# ITU_Rocket_Main_Board.net
KiCad netlist of a schematic drawn in Altium Designer
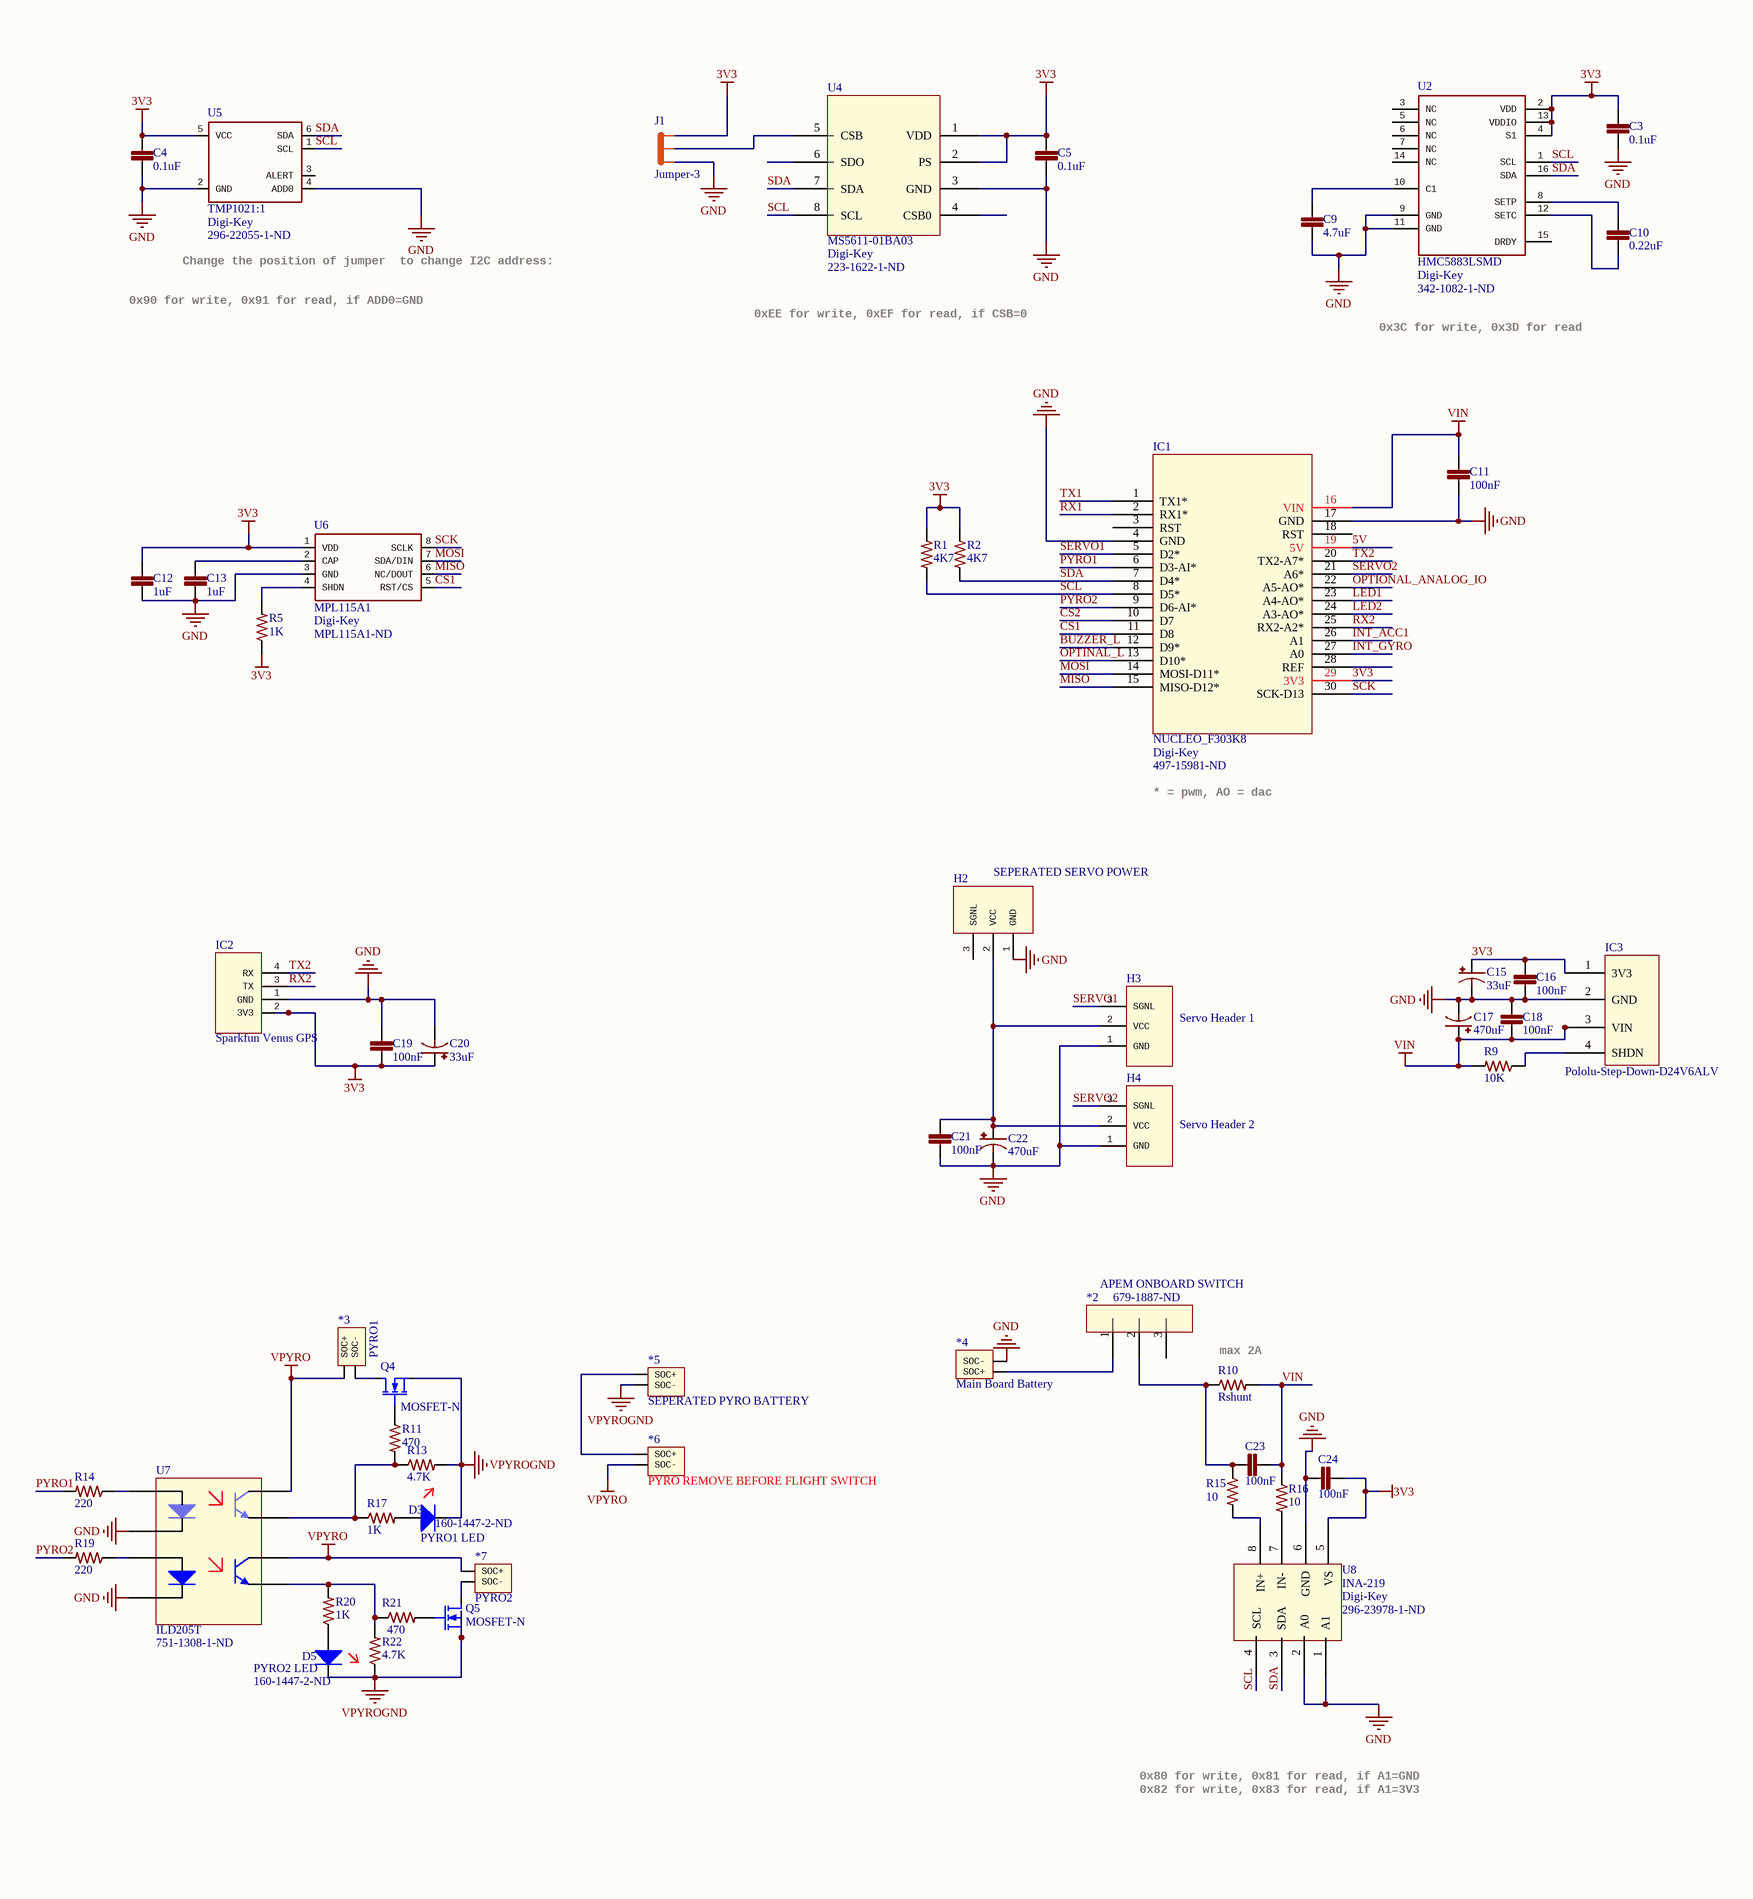
[diagram p0: ITU_Rocket_Main_Board.SchDoc, left]
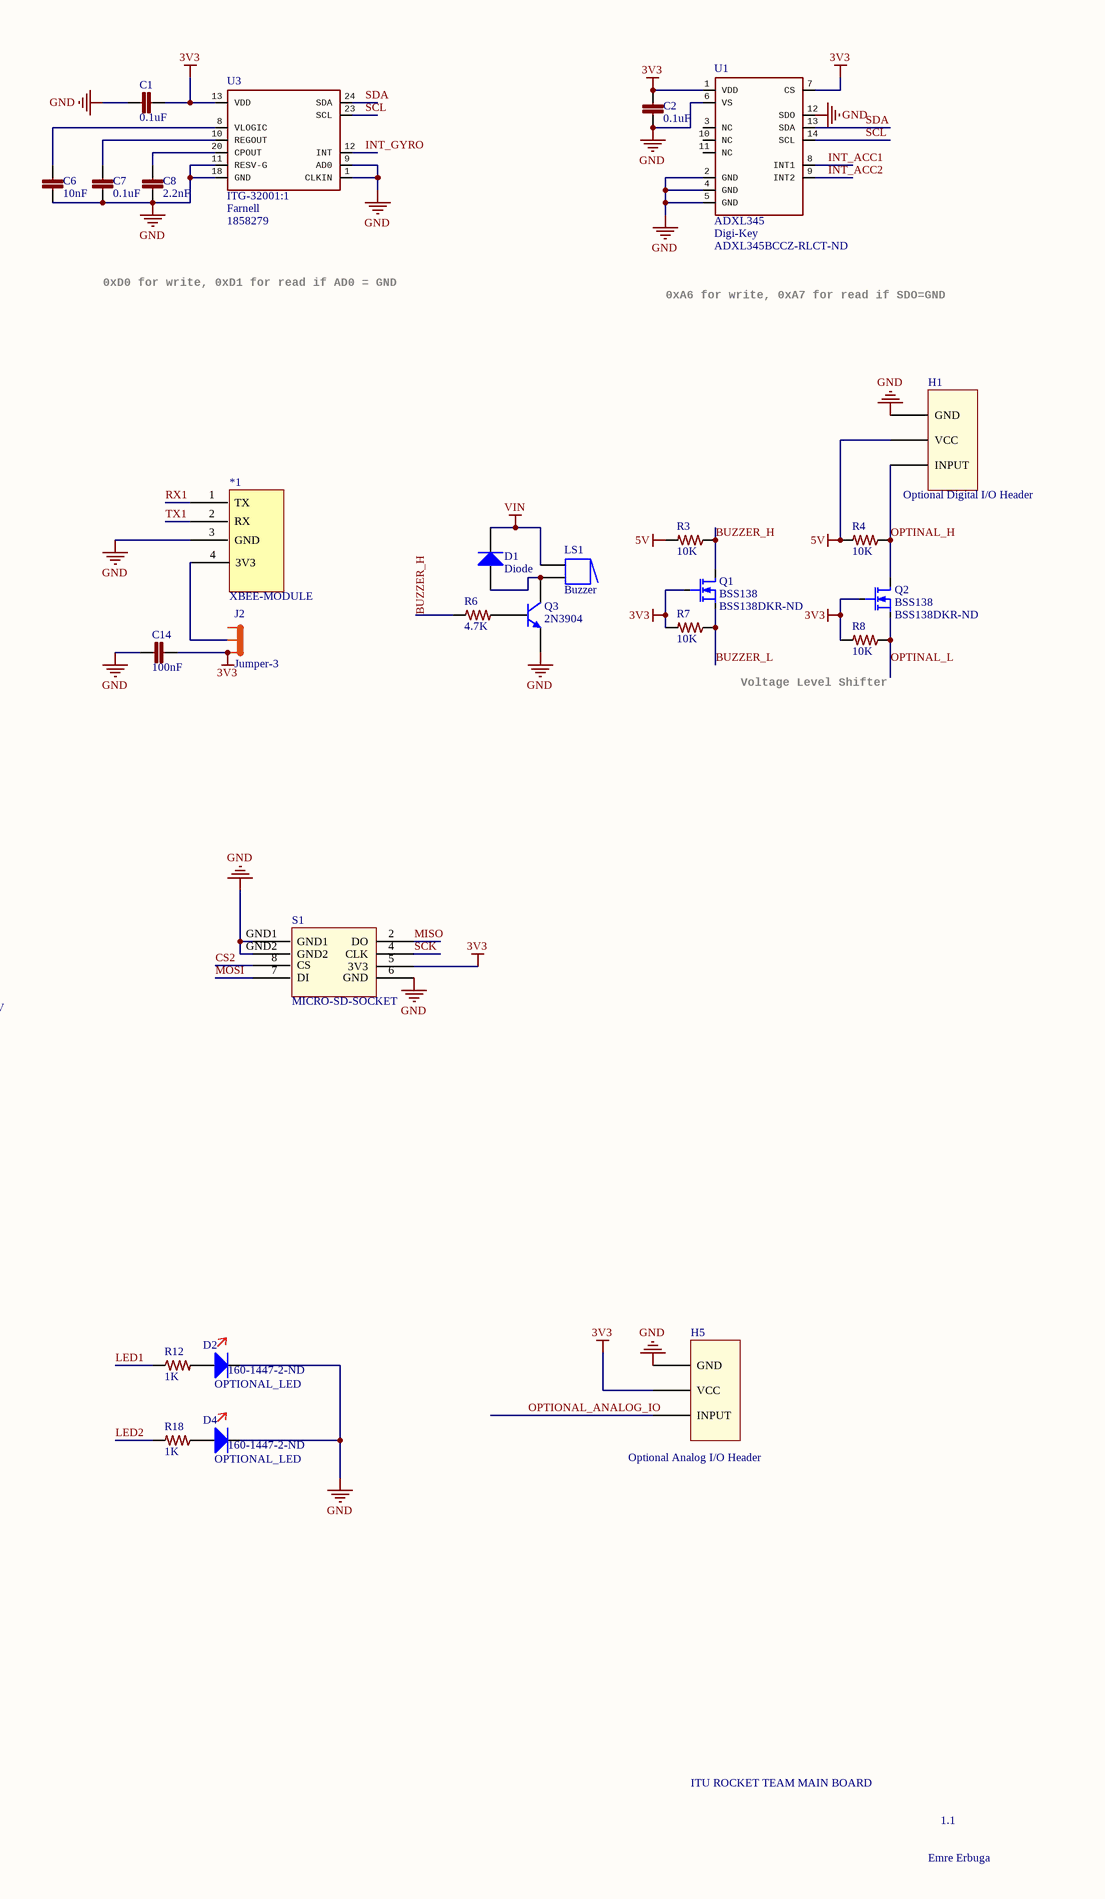
[diagram p1: ITU_Rocket_Main_Board.SchDoc, right]

(export (version "E")
  (design (tool "Eeschema 10.0.6"))
  (components
    (comp (ref "*1")
      (value "XBEE-MODULE")
      (footprint "XBEE-MODULE")
      (libsource (lib "ITU_Rocket_Main_Board") (part "XBEE-MODULE"))
    )
    (comp (ref "*2")
      (value "APEM ONBOARD SWITCH")
      (footprint "Switch_5.08")
      (description "SWITCH SLIDE SPDT 4A 125V")
      (fields
        (field (name "MANUFACTURER") "Apem Inc.")
        (field (name "MANUFACTURER PART NUMBER") "25136NAH")
        (field (name "SUPPLIER PART NUMBER 1") "679-1887-ND")
      )
      (libsource (lib "ITU_Rocket_Main_Board") (part "25136NAH"))
    )
    (comp (ref "*3")
      (value "PYRO1")
      (footprint "POWER_SOCKET")
      (libsource (lib "ITU_Rocket_Main_Board") (part "Power-Terminal"))
    )
    (comp (ref "*4")
      (value "Main Board Battery")
      (footprint "POWER_SOCKET")
      (libsource (lib "") (part "Power-Terminal_2"))
    )
    (comp (ref "*5")
      (value "SEPERATED PYRO BATTERY")
      (footprint "POWER_SOCKET")
      (libsource (lib "") (part "Power-Terminal_1"))
    )
    (comp (ref "*6")
      (value "PYRO REMOVE BEFORE FLIGHT SWITCH")
      (footprint "POWER_SOCKET")
      (libsource (lib "") (part "Power-Terminal_1"))
    )
    (comp (ref "*7")
      (value "PYRO2")
      (footprint "POWER_SOCKET")
      (libsource (lib "") (part "Power-Terminal_1"))
    )
    (comp (ref "C1")
      (value "0.1uF")
      (footprint "0603-CAP")
      (fields
        (field (name "MANUFACTURER") "Fairchild Semiconductor")
        (field (name "MANUFACTURER PART NUMBER") "BSS138")
      )
      (libsource (lib "") (part "CAP0603-CAP_1"))
    )
    (comp (ref "C2")
      (value "0.1uF")
      (footprint "0603-CAP")
      (fields
        (field (name "MANUFACTURER") "Fairchild Semiconductor")
        (field (name "MANUFACTURER PART NUMBER") "BSS138")
      )
      (libsource (lib "ITU_Rocket_Main_Board") (part "CAP0603-CAP"))
    )
    (comp (ref "C3")
      (value "0.1uF")
      (footprint "0603-CAP")
      (fields
        (field (name "MANUFACTURER") "Fairchild Semiconductor")
        (field (name "MANUFACTURER PART NUMBER") "BSS138")
      )
      (libsource (lib "ITU_Rocket_Main_Board") (part "CAP0603-CAP"))
    )
    (comp (ref "C4")
      (value "0.1uF")
      (footprint "0603-CAP")
      (fields
        (field (name "MANUFACTURER") "Fairchild Semiconductor")
        (field (name "MANUFACTURER PART NUMBER") "BSS138")
      )
      (libsource (lib "ITU_Rocket_Main_Board") (part "CAP0603-CAP"))
    )
    (comp (ref "C5")
      (value "0.1uF")
      (footprint "0603-CAP")
      (fields
        (field (name "MANUFACTURER") "Fairchild Semiconductor")
        (field (name "MANUFACTURER PART NUMBER") "BSS138")
      )
      (libsource (lib "ITU_Rocket_Main_Board") (part "CAP0603-CAP"))
    )
    (comp (ref "C6")
      (value "10nF")
      (footprint "0603-CAP")
      (fields
        (field (name "MANUFACTURER") "Fairchild Semiconductor")
        (field (name "MANUFACTURER PART NUMBER") "BSS138")
      )
      (libsource (lib "ITU_Rocket_Main_Board") (part "CAP0603-CAP"))
    )
    (comp (ref "C7")
      (value "0.1uF")
      (footprint "0603-CAP")
      (fields
        (field (name "MANUFACTURER") "Fairchild Semiconductor")
        (field (name "MANUFACTURER PART NUMBER") "BSS138")
      )
      (libsource (lib "ITU_Rocket_Main_Board") (part "CAP0603-CAP"))
    )
    (comp (ref "C8")
      (value "2.2nF")
      (footprint "0603-CAP")
      (fields
        (field (name "MANUFACTURER") "Fairchild Semiconductor")
        (field (name "MANUFACTURER PART NUMBER") "BSS138")
      )
      (libsource (lib "ITU_Rocket_Main_Board") (part "CAP0603-CAP"))
    )
    (comp (ref "C9")
      (value "4.7uF")
      (footprint "CAP0805-NP")
      (fields
        (field (name "MANUFACTURER") "Fairchild Semiconductor")
        (field (name "MANUFACTURER PART NUMBER") "BSS138")
      )
      (libsource (lib "ITU_Rocket_Main_Board") (part "CAP0603-CAP"))
    )
    (comp (ref "C10")
      (value "0.22uF")
      (footprint "0603-CAP")
      (fields
        (field (name "MANUFACTURER") "Fairchild Semiconductor")
        (field (name "MANUFACTURER PART NUMBER") "BSS138")
      )
      (libsource (lib "ITU_Rocket_Main_Board") (part "CAP0603-CAP"))
    )
    (comp (ref "C11")
      (value "100nF")
      (footprint "0603-CAP")
      (fields
        (field (name "MANUFACTURER") "Fairchild Semiconductor")
        (field (name "MANUFACTURER PART NUMBER") "BSS138")
      )
      (libsource (lib "ITU_Rocket_Main_Board") (part "CAP0603-CAP"))
    )
    (comp (ref "C12")
      (value "1uF")
      (footprint "0603-CAP")
      (fields
        (field (name "MANUFACTURER") "Fairchild Semiconductor")
        (field (name "MANUFACTURER PART NUMBER") "BSS138")
      )
      (libsource (lib "ITU_Rocket_Main_Board") (part "CAP0603-CAP"))
    )
    (comp (ref "C13")
      (value "1uF")
      (footprint "0603-CAP")
      (fields
        (field (name "MANUFACTURER") "Fairchild Semiconductor")
        (field (name "MANUFACTURER PART NUMBER") "BSS138")
      )
      (libsource (lib "ITU_Rocket_Main_Board") (part "CAP0603-CAP"))
    )
    (comp (ref "C14")
      (value "100nF")
      (footprint "0603-CAP")
      (fields
        (field (name "MANUFACTURER") "Fairchild Semiconductor")
        (field (name "MANUFACTURER PART NUMBER") "BSS138")
      )
      (libsource (lib "") (part "CAP0603-CAP_1"))
    )
    (comp (ref "C15")
      (value "33uF")
      (footprint "PANASONIC_C")
      (libsource (lib "") (part "CAP_PANASONIC_C_1"))
    )
    (comp (ref "C16")
      (value "100nF")
      (footprint "0603-CAP")
      (fields
        (field (name "MANUFACTURER") "Fairchild Semiconductor")
        (field (name "MANUFACTURER PART NUMBER") "BSS138")
      )
      (libsource (lib "ITU_Rocket_Main_Board") (part "CAP0603-CAP"))
    )
    (comp (ref "C17")
      (value "470uF")
      (footprint "PANASONIC_E")
      (libsource (lib "") (part "CAP_PANASONIC_F_1"))
    )
    (comp (ref "C18")
      (value "100nF")
      (footprint "0603-CAP")
      (fields
        (field (name "MANUFACTURER") "Fairchild Semiconductor")
        (field (name "MANUFACTURER PART NUMBER") "BSS138")
      )
      (libsource (lib "ITU_Rocket_Main_Board") (part "CAP0603-CAP"))
    )
    (comp (ref "C19")
      (value "100nF")
      (footprint "0603-CAP")
      (fields
        (field (name "MANUFACTURER") "Fairchild Semiconductor")
        (field (name "MANUFACTURER PART NUMBER") "BSS138")
      )
      (libsource (lib "ITU_Rocket_Main_Board") (part "CAP0603-CAP"))
    )
    (comp (ref "C20")
      (value "33uF")
      (footprint "PANASONIC_C")
      (libsource (lib "ITU_Rocket_Main_Board") (part "CAP_PANASONIC_C"))
    )
    (comp (ref "C21")
      (value "100nF")
      (footprint "0603-CAP")
      (fields
        (field (name "MANUFACTURER") "Fairchild Semiconductor")
        (field (name "MANUFACTURER PART NUMBER") "BSS138")
      )
      (libsource (lib "ITU_Rocket_Main_Board") (part "CAP0603-CAP"))
    )
    (comp (ref "C22")
      (value "470uF")
      (footprint "PANASONIC_E")
      (libsource (lib "ITU_Rocket_Main_Board") (part "CAP_PANASONIC_F"))
    )
    (comp (ref "C23")
      (value "100nF")
      (footprint "0603-CAP")
      (fields
        (field (name "MANUFACTURER") "Fairchild Semiconductor")
        (field (name "MANUFACTURER PART NUMBER") "BSS138")
      )
      (libsource (lib "") (part "CAP0603-CAP_1"))
    )
    (comp (ref "C24")
      (value "100nF")
      (footprint "0603-CAP")
      (fields
        (field (name "MANUFACTURER") "Fairchild Semiconductor")
        (field (name "MANUFACTURER PART NUMBER") "BSS138")
      )
      (libsource (lib "") (part "CAP0603-CAP_1"))
    )
    (comp (ref "D1")
      (value "Diode")
      (footprint "SMB")
      (description "Default Diode")
      (fields (field (name "PUBLISHER") "Altium Limited"))
      (libsource (lib "ITU_Rocket_Main_Board") (part "Diode"))
    )
    (comp (ref "D2")
      (value "OPTIONAL_LED")
      (footprint "0603-SMD-LED")
      (description "LED RED CLEAR 0603 SMD")
      (fields
        (field (name "MANUFACTURER") "Lite-On Inc.")
        (field (name "MANUFACTURER PART NUMBER") "LTST-C191KRKT")
        (field (name "SUPPLIER PART NUMBER 1") "160-1447-2-ND")
      )
      (libsource (lib "ITU_Rocket_Main_Board") (part "LTST-C191KRKT"))
    )
    (comp (ref "D3")
      (value "PYRO1 LED")
      (footprint "0603-SMD-LED")
      (description "LED RED CLEAR 0603 SMD")
      (fields
        (field (name "MANUFACTURER") "Lite-On Inc.")
        (field (name "MANUFACTURER PART NUMBER") "LTST-C191KRKT")
        (field (name "SUPPLIER PART NUMBER 1") "160-1447-2-ND")
      )
      (libsource (lib "ITU_Rocket_Main_Board") (part "LTST-C191KRKT"))
    )
    (comp (ref "D4")
      (value "OPTIONAL_LED")
      (footprint "0603-SMD-LED")
      (description "LED RED CLEAR 0603 SMD")
      (fields
        (field (name "MANUFACTURER") "Lite-On Inc.")
        (field (name "MANUFACTURER PART NUMBER") "LTST-C191KRKT")
        (field (name "SUPPLIER PART NUMBER 1") "160-1447-2-ND")
      )
      (libsource (lib "ITU_Rocket_Main_Board") (part "LTST-C191KRKT"))
    )
    (comp (ref "D5")
      (value "PYRO2 LED")
      (footprint "0603-SMD-LED")
      (description "LED RED CLEAR 0603 SMD")
      (fields
        (field (name "MANUFACTURER") "Lite-On Inc.")
        (field (name "MANUFACTURER PART NUMBER") "LTST-C191KRKT")
        (field (name "SUPPLIER PART NUMBER 1") "160-1447-2-ND")
      )
      (libsource (lib "ITU_Rocket_Main_Board") (part "LTST-C191KRKT"))
    )
    (comp (ref "H1")
      (value "Header")
      (footprint "HEADER_3")
      (libsource (lib "ITU_Rocket_Main_Board") (part "HEADER_3"))
    )
    (comp (ref "H2")
      (value "SEPERATED SERVO POWER")
      (footprint "SERVO")
      (libsource (lib "") (part "Servo-Header_1"))
    )
    (comp (ref "H3")
      (value "Servo Header 1")
      (footprint "SERVO")
      (libsource (lib "ITU_Rocket_Main_Board") (part "Servo-Header"))
    )
    (comp (ref "H4")
      (value "Servo Header 2")
      (footprint "SERVO")
      (libsource (lib "ITU_Rocket_Main_Board") (part "Servo-Header"))
    )
    (comp (ref "H5")
      (value "Header")
      (footprint "HEADER_3")
      (libsource (lib "ITU_Rocket_Main_Board") (part "HEADER_3"))
    )
    (comp (ref "IC1")
      (value "NUCLEO_F303K8")
      (footprint "nucleo_f303")
      (fields (field (name "SUPPLIER 1") "Digi-Key") (field (name "SUPPLIER PART NUMBER 1") "497-15981-ND"))
      (libsource (lib "ITU_Rocket_Main_Board") (part "NUCLEO-32-F303K8"))
    )
    (comp (ref "IC2")
      (value "Sparkfun Venus GPS")
      (footprint "SPARKFUN_VENUS_GPS")
      (libsource (lib "ITU_Rocket_Main_Board") (part "Sparkfun-Venus-Gps"))
    )
    (comp (ref "IC3")
      (value "Pololu-Step-Down-D24V6ALV")
      (footprint "Pololu-D24V6ALV")
      (libsource (lib "ITU_Rocket_Main_Board") (part "Pololu-D24V6ALV"))
    )
    (comp (ref "J1")
      (value "Jumper-3")
      (footprint "SJ_3")
      (libsource (lib "ITU_Rocket_Main_Board") (part "Jumper-3"))
    )
    (comp (ref "J2")
      (value "Jumper-3")
      (footprint "SJ_3")
      (libsource (lib "ITU_Rocket_Main_Board") (part "Jumper-3"))
    )
    (comp (ref "LS1")
      (value "Buzzer")
      (footprint "Buzzer-A3")
      (description "Magnetic Transducer Buzzer")
      (fields (field (name "PUBLISHER") "Altium Limited"))
      (libsource (lib "ITU_Rocket_Main_Board") (part "Buzzer"))
    )
    (comp (ref "Q1")
      (value "BSS138")
      (footprint "SOT23-3")
      (description "MOSFET N-CH 50V 220MA SOT-23")
      (fields
        (field (name "MANUFACTURER") "Fairchild Semiconductor")
        (field (name "SUPPLIER PART NUMBER 1") "BSS138DKR-ND")
      )
      (libsource (lib "ITU_Rocket_Main_Board") (part "BSS138"))
    )
    (comp (ref "Q2")
      (value "BSS138")
      (footprint "SOT23-3")
      (description "MOSFET N-CH 50V 220MA SOT-23")
      (fields
        (field (name "MANUFACTURER") "Fairchild Semiconductor")
        (field (name "SUPPLIER PART NUMBER 1") "BSS138DKR-ND")
      )
      (libsource (lib "ITU_Rocket_Main_Board") (part "BSS138"))
    )
    (comp (ref "Q3")
      (value "2N3904")
      (footprint "TO-92A")
      (description "NPN General Purpose Amplifier")
      (fields (field (name "PUBLISHER") "Altium Limited"))
      (libsource (lib "ITU_Rocket_Main_Board") (part "2N3904"))
    )
    (comp (ref "Q4")
      (value "MOSFET-N")
      (footprint "to-252")
      (description "N-Channel MOSFET")
      (fields (field (name "PUBLISHER") "Altium Limited"))
      (libsource (lib "ITU_Rocket_Main_Board") (part "MOSFET-N"))
    )
    (comp (ref "Q5")
      (value "MOSFET-N")
      (footprint "to-252")
      (description "N-Channel MOSFET")
      (fields (field (name "PUBLISHER") "Altium Limited"))
      (libsource (lib "ITU_Rocket_Main_Board") (part "MOSFET-N"))
    )
    (comp (ref "R1")
      (value "4K7")
      (footprint "0603-RES")
      (libsource (lib "ITU_Rocket_Main_Board") (part "RESISTOR0603"))
    )
    (comp (ref "R2")
      (value "4K7")
      (footprint "0603-RES")
      (libsource (lib "ITU_Rocket_Main_Board") (part "RESISTOR0603"))
    )
    (comp (ref "R3")
      (value "10K")
      (footprint "0603-RES")
      (libsource (lib "ITU_Rocket_Main_Board") (part "RESISTOR0603"))
    )
    (comp (ref "R4")
      (value "10K")
      (footprint "0603-RES")
      (libsource (lib "ITU_Rocket_Main_Board") (part "RESISTOR0603"))
    )
    (comp (ref "R5")
      (value "1K")
      (footprint "0603-RES")
      (libsource (lib "ITU_Rocket_Main_Board") (part "RESISTOR0603"))
    )
    (comp (ref "R6")
      (value "4.7K")
      (footprint "0603-RES")
      (libsource (lib "ITU_Rocket_Main_Board") (part "RESISTOR0603"))
    )
    (comp (ref "R7")
      (value "10K")
      (footprint "0603-RES")
      (libsource (lib "ITU_Rocket_Main_Board") (part "RESISTOR0603"))
    )
    (comp (ref "R8")
      (value "10K")
      (footprint "0603-RES")
      (libsource (lib "ITU_Rocket_Main_Board") (part "RESISTOR0603"))
    )
    (comp (ref "R9")
      (value "10K")
      (footprint "0603-RES")
      (libsource (lib "ITU_Rocket_Main_Board") (part "RESISTOR0603"))
    )
    (comp (ref "R10")
      (value "Rshunt")
      (footprint "Resistor-Shunt")
      (libsource (lib "ITU_Rocket_Main_Board") (part "Resistor-Shunt"))
    )
    (comp (ref "R11")
      (value "470")
      (footprint "0603-RES")
      (libsource (lib "ITU_Rocket_Main_Board") (part "RESISTOR0603"))
    )
    (comp (ref "R12")
      (value "1K")
      (footprint "0603-RES")
      (libsource (lib "ITU_Rocket_Main_Board") (part "RESISTOR0603"))
    )
    (comp (ref "R13")
      (value "4.7K")
      (footprint "0603-RES")
      (libsource (lib "ITU_Rocket_Main_Board") (part "RESISTOR0603"))
    )
    (comp (ref "R14")
      (value "220")
      (footprint "0603-RES")
      (libsource (lib "ITU_Rocket_Main_Board") (part "RESISTOR0603"))
    )
    (comp (ref "R15")
      (value "10")
      (footprint "0603-RES")
      (libsource (lib "ITU_Rocket_Main_Board") (part "RESISTOR0603"))
    )
    (comp (ref "R16")
      (value "10")
      (footprint "0603-RES")
      (libsource (lib "ITU_Rocket_Main_Board") (part "RESISTOR0603"))
    )
    (comp (ref "R17")
      (value "1K")
      (footprint "0603-RES")
      (libsource (lib "ITU_Rocket_Main_Board") (part "RESISTOR0603"))
    )
    (comp (ref "R18")
      (value "1K")
      (footprint "0603-RES")
      (libsource (lib "ITU_Rocket_Main_Board") (part "RESISTOR0603"))
    )
    (comp (ref "R19")
      (value "220")
      (footprint "0603-RES")
      (libsource (lib "ITU_Rocket_Main_Board") (part "RESISTOR0603"))
    )
    (comp (ref "R20")
      (value "1K")
      (footprint "0603-RES")
      (libsource (lib "ITU_Rocket_Main_Board") (part "RESISTOR0603"))
    )
    (comp (ref "R21")
      (value "470")
      (footprint "0603-RES")
      (libsource (lib "ITU_Rocket_Main_Board") (part "RESISTOR0603"))
    )
    (comp (ref "R22")
      (value "4.7K")
      (footprint "0603-RES")
      (libsource (lib "ITU_Rocket_Main_Board") (part "RESISTOR0603"))
    )
    (comp (ref "S1")
      (value "MICRO-SD-SOCKET")
      (footprint "micro-sd")
      (libsource (lib "ITU_Rocket_Main_Board") (part "MICRO-SD-SOCKET"))
    )
    (comp (ref "U1")
      (value "ADXL345")
      (footprint "LGA14")
      (fields
        (field (name "SUPPLIER 1") "Digi-Key")
        (field (name "SUPPLIER PART NUMBER 1") "ADXL345BCCZ-RLCT-ND")
      )
      (libsource (lib "ITU_Rocket_Main_Board") (part "ADXL345"))
    )
    (comp (ref "U2")
      (value "HMC5883LSMD")
      (footprint "16LPCC")
      (fields (field (name "SUPPLIER 1") "Digi-Key") (field (name "SUPPLIER PART NUMBER 1") "342-1082-1-ND"))
      (libsource (lib "ITU_Rocket_Main_Board") (part "HMC5883LSMD"))
    )
    (comp (ref "U3")
      (value "ITG-32001:1")
      (footprint "QFN-24_ITG3200_1:1")
      (fields (field (name "SUPPLIER 1") "Farnell") (field (name "SUPPLIER PART NUMBER 1") "1858279"))
      (libsource (lib "ITU_Rocket_Main_Board") (part "ITG-32001{colon}1"))
    )
    (comp (ref "U4")
      (value "MS5611-01BA03")
      (footprint "MS5611-01BA03")
      (fields (field (name "SUPPLIER 1") "Digi-Key") (field (name "SUPPLIER PART NUMBER 1") "223-1622-1-ND"))
      (libsource (lib "ITU_Rocket_Main_Board") (part "MS5611-01BA03"))
    )
    (comp (ref "U5")
      (value "TMP1021:1")
      (footprint "SOT563-2")
      (fields (field (name "SUPPLIER 1") "Digi-Key") (field (name "SUPPLIER PART NUMBER 1") "296-22055-1-ND"))
      (libsource (lib "ITU_Rocket_Main_Board") (part "TMP1021{colon}1"))
    )
    (comp (ref "U6")
      (value "MPL115A1")
      (footprint "LGA8")
      (fields (field (name "SUPPLIER 1") "Digi-Key") (field (name "SUPPLIER PART NUMBER 1") "MPL115A1-ND"))
      (libsource (lib "ITU_Rocket_Main_Board") (part "MPL115A"))
    )
    (comp (ref "U7")
      (value "ILD205T")
      (footprint "SOIC-8-ILD205T")
      (description "OPTOISOLTR 4KV 2CH TRANS 8-SOIC")
      (fields
        (field (name "MANUFACTURER") "Vishay Semiconductor Opto Division")
        (field (name "SUPPLIER PART NUMBER 1") "751-1308-1-ND")
      )
      (libsource (lib "ITU_Rocket_Main_Board") (part "ILD205T"))
    )
    (comp (ref "U8")
      (value "INA-219")
      (footprint "SOIC127P600X175-8N")
      (fields (field (name "SUPPLIER 1") "Digi-Key") (field (name "SUPPLIER PART NUMBER 1") "296-23978-1-ND"))
      (libsource (lib "ITU_Rocket_Main_Board") (part "INA-219"))
    )
  )
  (nets
    (net (code "1") (name "/BUZZER_H") (class "Default")
      (node (ref "Q1") (pin "D") (pinfunction "D_D") (pintype "passive"))
      (node (ref "R3") (pin "1") (pinfunction "1_1") (pintype "passive"))
      (node (ref "R6") (pin "1") (pinfunction "1_1") (pintype "passive"))
    )
    (net (code "2") (name "/BUZZER_L") (class "Default")
      (node (ref "IC1") (pin "12") (pinfunction "D9*_12") (pintype "passive"))
      (node (ref "Q1") (pin "S") (pinfunction "S_S") (pintype "passive"))
      (node (ref "R7") (pin "1") (pinfunction "1_1") (pintype "passive"))
    )
    (net (code "3") (name "/CS1") (class "Default")
      (node (ref "IC1") (pin "11") (pinfunction "D8_11") (pintype "passive"))
      (node (ref "U6") (pin "5") (pinfunction "RST/CS_5") (pintype "passive"))
    )
    (net (code "4") (name "/CS2") (class "Default")
      (node (ref "IC1") (pin "10") (pinfunction "D7_10") (pintype "passive"))
      (node (ref "S1") (pin "8") (pinfunction "CS_8") (pintype "passive"))
    )
    (net (code "5") (name "/INT_ACC1") (class "Default")
      (node (ref "IC1") (pin "26") (pinfunction "A1_26") (pintype "passive"))
      (node (ref "U1") (pin "8") (pinfunction "INT1_8") (pintype "passive"))
    )
    (net (code "6") (name "/INT_ACC2") (class "Default")
      (node (ref "U1") (pin "9") (pinfunction "INT2_9") (pintype "passive"))
    )
    (net (code "7") (name "/INT_GYRO") (class "Default")
      (node (ref "IC1") (pin "27") (pinfunction "A0_27") (pintype "passive"))
      (node (ref "U3") (pin "12") (pinfunction "INT_12") (pintype "passive"))
    )
    (net (code "8") (name "/LED1") (class "Default")
      (node (ref "IC1") (pin "23") (pinfunction "A4-AO*_23") (pintype "passive"))
      (node (ref "R12") (pin "1") (pinfunction "1_1") (pintype "passive"))
    )
    (net (code "9") (name "/LED2") (class "Default")
      (node (ref "IC1") (pin "24") (pinfunction "A3-AO*_24") (pintype "passive"))
      (node (ref "R18") (pin "2") (pinfunction "2_2") (pintype "passive"))
    )
    (net (code "10") (name "/MISO") (class "Default")
      (node (ref "IC1") (pin "15") (pinfunction "MISO-D12*_15") (pintype "passive"))
      (node (ref "S1") (pin "2") (pinfunction "DO_2") (pintype "passive"))
      (node (ref "U6") (pin "6") (pinfunction "NC/DOUT_6") (pintype "passive"))
    )
    (net (code "11") (name "/MOSI") (class "Default")
      (node (ref "IC1") (pin "14") (pinfunction "MOSI-D11*_14") (pintype "passive"))
      (node (ref "S1") (pin "7") (pinfunction "DI_7") (pintype "passive"))
      (node (ref "U6") (pin "7") (pinfunction "SDA/DIN_7") (pintype "passive"))
    )
    (net (code "12") (name "/OPTINAL_H") (class "Default")
      (node (ref "H1") (pin "3") (pinfunction "INPUT_3") (pintype "passive"))
      (node (ref "Q2") (pin "D") (pinfunction "D_D") (pintype "passive"))
      (node (ref "R4") (pin "1") (pinfunction "1_1") (pintype "passive"))
    )
    (net (code "13") (name "/OPTINAL_L") (class "Default")
      (node (ref "IC1") (pin "13") (pinfunction "D10*_13") (pintype "passive"))
      (node (ref "Q2") (pin "S") (pinfunction "S_S") (pintype "passive"))
      (node (ref "R8") (pin "1") (pinfunction "1_1") (pintype "passive"))
    )
    (net (code "14") (name "/OPTIONAL_ANALOG_IO") (class "Default")
      (node (ref "H5") (pin "3") (pinfunction "INPUT_3") (pintype "passive"))
      (node (ref "IC1") (pin "22") (pinfunction "A5-AO*_22") (pintype "passive"))
    )
    (net (code "15") (name "/PYRO1") (class "Default")
      (node (ref "IC1") (pin "6") (pinfunction "D3-AI*_6") (pintype "passive"))
      (node (ref "R14") (pin "2") (pinfunction "2_2") (pintype "passive"))
    )
    (net (code "16") (name "/PYRO2") (class "Default")
      (node (ref "IC1") (pin "9") (pinfunction "D6-AI*_9") (pintype "passive"))
      (node (ref "R19") (pin "2") (pinfunction "2_2") (pintype "passive"))
    )
    (net (code "17") (name "/RX1") (class "Default")
      (node (ref "*1") (pin "1") (pinfunction "TX_1") (pintype "passive"))
      (node (ref "IC1") (pin "2") (pinfunction "RX1*_2") (pintype "passive"))
    )
    (net (code "18") (name "/RX2") (class "Default")
      (node (ref "IC1") (pin "25") (pinfunction "RX2-A2*_25") (pintype "passive"))
      (node (ref "IC2") (pin "3") (pinfunction "TX_3") (pintype "passive"))
    )
    (net (code "19") (name "/SCK") (class "Default")
      (node (ref "IC1") (pin "30") (pinfunction "SCK-D13_30") (pintype "passive"))
      (node (ref "S1") (pin "4") (pinfunction "CLK_4") (pintype "passive"))
      (node (ref "U6") (pin "8") (pinfunction "SCLK_8") (pintype "passive"))
    )
    (net (code "20") (name "/SCL") (class "Default")
      (node (ref "IC1") (pin "8") (pinfunction "D5*_8") (pintype "passive"))
      (node (ref "R1") (pin "2") (pinfunction "2_2") (pintype "passive"))
      (node (ref "U1") (pin "14") (pinfunction "SCL_14") (pintype "passive"))
      (node (ref "U2") (pin "1") (pinfunction "SCL_1") (pintype "passive"))
      (node (ref "U3") (pin "23") (pinfunction "SCL_23") (pintype "passive"))
      (node (ref "U4") (pin "8") (pinfunction "SCL_8") (pintype "passive"))
      (node (ref "U5") (pin "1") (pinfunction "SCL_1") (pintype "passive"))
      (node (ref "U8") (pin "4") (pinfunction "SCL_4") (pintype "passive"))
    )
    (net (code "21") (name "/SDA") (class "Default")
      (node (ref "IC1") (pin "7") (pinfunction "D4*_7") (pintype "passive"))
      (node (ref "R2") (pin "2") (pinfunction "2_2") (pintype "passive"))
      (node (ref "U1") (pin "13") (pinfunction "SDA_13") (pintype "passive"))
      (node (ref "U2") (pin "16") (pinfunction "SDA_16") (pintype "passive"))
      (node (ref "U3") (pin "24") (pinfunction "SDA_24") (pintype "passive"))
      (node (ref "U4") (pin "7") (pinfunction "SDA_7") (pintype "passive"))
      (node (ref "U5") (pin "6") (pinfunction "SDA_6") (pintype "passive"))
      (node (ref "U8") (pin "3") (pinfunction "SDA_3") (pintype "passive"))
    )
    (net (code "22") (name "/SERVO1") (class "Default")
      (node (ref "H3") (pin "3") (pinfunction "SGNL_3") (pintype "passive"))
      (node (ref "IC1") (pin "5") (pinfunction "D2*_5") (pintype "passive"))
    )
    (net (code "23") (name "/SERVO2") (class "Default")
      (node (ref "H4") (pin "3") (pinfunction "SGNL_3") (pintype "passive"))
      (node (ref "IC1") (pin "21") (pinfunction "A6*_21") (pintype "passive"))
    )
    (net (code "24") (name "/TX1") (class "Default")
      (node (ref "*1") (pin "2") (pinfunction "RX_2") (pintype "passive"))
      (node (ref "IC1") (pin "1") (pinfunction "TX1*_1") (pintype "passive"))
    )
    (net (code "25") (name "/TX2") (class "Default")
      (node (ref "IC1") (pin "20") (pinfunction "TX2-A7*_20") (pintype "passive"))
      (node (ref "IC2") (pin "4") (pinfunction "RX_4") (pintype "passive"))
    )
    (net (code "26") (name "3V3") (class "Default")
      (node (ref "C1") (pin "2") (pinfunction "2_2") (pintype "passive"))
      (node (ref "C12") (pin "1") (pinfunction "1_1") (pintype "passive"))
      (node (ref "C14") (pin "2") (pinfunction "2_2") (pintype "passive"))
      (node (ref "C15") (pin "+") (pinfunction "+_+") (pintype "passive"))
      (node (ref "C16") (pin "1") (pinfunction "1_1") (pintype "passive"))
      (node (ref "C19") (pin "2") (pinfunction "2_2") (pintype "passive"))
      (node (ref "C2") (pin "1") (pinfunction "1_1") (pintype "passive"))
      (node (ref "C20") (pin "+") (pinfunction "+_+") (pintype "passive"))
      (node (ref "C24") (pin "2") (pinfunction "2_2") (pintype "passive"))
      (node (ref "C3") (pin "1") (pinfunction "1_1") (pintype "passive"))
      (node (ref "C4") (pin "1") (pinfunction "1_1") (pintype "passive"))
      (node (ref "C5") (pin "1") (pinfunction "1_1") (pintype "passive"))
      (node (ref "H5") (pin "2") (pinfunction "VCC_2") (pintype "passive"))
      (node (ref "IC1") (pin "29") (pinfunction "3V3_29") (pintype "passive"))
      (node (ref "IC2") (pin "2") (pinfunction "3V3_2") (pintype "passive"))
      (node (ref "IC3") (pin "1") (pinfunction "3V3_1") (pintype "passive"))
      (node (ref "J1") (pin "3") (pintype "passive"))
      (node (ref "J2") (pin "3") (pintype "passive"))
      (node (ref "Q1") (pin "G") (pinfunction "G_G") (pintype "passive"))
      (node (ref "Q2") (pin "G") (pinfunction "G_G") (pintype "passive"))
      (node (ref "R1") (pin "1") (pinfunction "1_1") (pintype "passive"))
      (node (ref "R2") (pin "1") (pinfunction "1_1") (pintype "passive"))
      (node (ref "R5") (pin "1") (pinfunction "1_1") (pintype "passive"))
      (node (ref "R7") (pin "2") (pinfunction "2_2") (pintype "passive"))
      (node (ref "R8") (pin "2") (pinfunction "2_2") (pintype "passive"))
      (node (ref "S1") (pin "5") (pinfunction "3V3_5") (pintype "passive"))
      (node (ref "U1") (pin "1") (pinfunction "VDD_1") (pintype "passive"))
      (node (ref "U1") (pin "7") (pinfunction "CS_7") (pintype "passive"))
      (node (ref "U2") (pin "13") (pinfunction "VDDIO_13") (pintype "passive"))
      (node (ref "U2") (pin "2") (pinfunction "VDD_2") (pintype "passive"))
      (node (ref "U2") (pin "4") (pinfunction "S1_4") (pintype "passive"))
      (node (ref "U3") (pin "13") (pinfunction "VDD_13") (pintype "passive"))
      (node (ref "U4") (pin "1") (pinfunction "VDD_1") (pintype "power_in"))
      (node (ref "U4") (pin "2") (pinfunction "PS_2") (pintype "passive"))
      (node (ref "U5") (pin "5") (pinfunction "VCC_5") (pintype "passive"))
      (node (ref "U6") (pin "1") (pinfunction "VDD_1") (pintype "passive"))
      (node (ref "U8") (pin "5") (pinfunction "VS_5") (pintype "passive"))
    )
    (net (code "27") (name "5V") (class "Default")
      (node (ref "H1") (pin "2") (pinfunction "VCC_2") (pintype "passive"))
      (node (ref "IC1") (pin "19") (pinfunction "5V_19") (pintype "passive"))
      (node (ref "R3") (pin "2") (pinfunction "2_2") (pintype "passive"))
      (node (ref "R4") (pin "2") (pinfunction "2_2") (pintype "passive"))
    )
    (net (code "28") (name "GND") (class "Default")
      (node (ref "*1") (pin "3") (pinfunction "GND_3") (pintype "passive"))
      (node (ref "*4") (pin "-") (pinfunction "SOC-_-") (pintype "passive"))
      (node (ref "C1") (pin "1") (pinfunction "1_1") (pintype "passive"))
      (node (ref "C11") (pin "2") (pinfunction "2_2") (pintype "passive"))
      (node (ref "C12") (pin "2") (pinfunction "2_2") (pintype "passive"))
      (node (ref "C13") (pin "2") (pinfunction "2_2") (pintype "passive"))
      (node (ref "C14") (pin "1") (pinfunction "1_1") (pintype "passive"))
      (node (ref "C15") (pin "-") (pinfunction "-_-") (pintype "passive"))
      (node (ref "C16") (pin "2") (pinfunction "2_2") (pintype "passive"))
      (node (ref "C17") (pin "-") (pinfunction "-_-") (pintype "passive"))
      (node (ref "C18") (pin "1") (pinfunction "1_1") (pintype "passive"))
      (node (ref "C19") (pin "1") (pinfunction "1_1") (pintype "passive"))
      (node (ref "C2") (pin "2") (pinfunction "2_2") (pintype "passive"))
      (node (ref "C20") (pin "-") (pinfunction "-_-") (pintype "passive"))
      (node (ref "C21") (pin "2") (pinfunction "2_2") (pintype "passive"))
      (node (ref "C22") (pin "-") (pinfunction "-_-") (pintype "passive"))
      (node (ref "C24") (pin "1") (pinfunction "1_1") (pintype "passive"))
      (node (ref "C3") (pin "2") (pinfunction "2_2") (pintype "passive"))
      (node (ref "C4") (pin "2") (pinfunction "2_2") (pintype "passive"))
      (node (ref "C5") (pin "2") (pinfunction "2_2") (pintype "passive"))
      (node (ref "C6") (pin "2") (pinfunction "2_2") (pintype "passive"))
      (node (ref "C7") (pin "2") (pinfunction "2_2") (pintype "passive"))
      (node (ref "C8") (pin "2") (pinfunction "2_2") (pintype "passive"))
      (node (ref "C9") (pin "2") (pinfunction "2_2") (pintype "passive"))
      (node (ref "D2") (pin "2") (pinfunction "K_2") (pintype "passive"))
      (node (ref "D4") (pin "2") (pinfunction "K_2") (pintype "passive"))
      (node (ref "H1") (pin "1") (pinfunction "GND_1") (pintype "passive"))
      (node (ref "H2") (pin "1") (pinfunction "GND_1") (pintype "passive"))
      (node (ref "H3") (pin "1") (pinfunction "GND_1") (pintype "passive"))
      (node (ref "H4") (pin "1") (pinfunction "GND_1") (pintype "passive"))
      (node (ref "H5") (pin "1") (pinfunction "GND_1") (pintype "passive"))
      (node (ref "IC1") (pin "17") (pinfunction "GND_17") (pintype "passive"))
      (node (ref "IC1") (pin "4") (pinfunction "GND_4") (pintype "passive"))
      (node (ref "IC2") (pin "1") (pinfunction "GND_1") (pintype "passive"))
      (node (ref "IC3") (pin "2") (pinfunction "GND_2") (pintype "passive"))
      (node (ref "J1") (pin "1") (pintype "passive"))
      (node (ref "Q3") (pin "1") (pinfunction "E_1") (pintype "passive"))
      (node (ref "S1") (pin "6") (pinfunction "GND_6") (pintype "passive"))
      (node (ref "S1") (pin "GND1") (pinfunction "GND1_GND1") (pintype "passive"))
      (node (ref "S1") (pin "GND2") (pinfunction "GND2_GND2") (pintype "passive"))
      (node (ref "U1") (pin "12") (pinfunction "SDO_12") (pintype "passive"))
      (node (ref "U1") (pin "2") (pinfunction "GND_2") (pintype "passive"))
      (node (ref "U1") (pin "4") (pinfunction "GND_4") (pintype "passive"))
      (node (ref "U1") (pin "5") (pinfunction "GND_5") (pintype "passive"))
      (node (ref "U1") (pin "6") (pinfunction "VS_6") (pintype "passive"))
      (node (ref "U2") (pin "11") (pinfunction "GND_11") (pintype "passive"))
      (node (ref "U2") (pin "9") (pinfunction "GND_9") (pintype "passive"))
      (node (ref "U3") (pin "1") (pinfunction "CLKIN_1") (pintype "passive"))
      (node (ref "U3") (pin "11") (pinfunction "RESV-G_11") (pintype "passive"))
      (node (ref "U3") (pin "18") (pinfunction "GND_18") (pintype "passive"))
      (node (ref "U3") (pin "9") (pinfunction "AD0_9") (pintype "passive"))
      (node (ref "U4") (pin "3") (pinfunction "GND_3") (pintype "power_in"))
      (node (ref "U5") (pin "2") (pinfunction "GND_2") (pintype "passive"))
      (node (ref "U5") (pin "4") (pinfunction "ADD0_4") (pintype "passive"))
      (node (ref "U6") (pin "3") (pinfunction "GND_3") (pintype "passive"))
      (node (ref "U7") (pin "2") (pinfunction "C_2") (pintype "passive"))
      (node (ref "U7") (pin "4") (pinfunction "C_4") (pintype "passive"))
      (node (ref "U8") (pin "1") (pinfunction "A1_1") (pintype "passive"))
      (node (ref "U8") (pin "2") (pinfunction "A0_2") (pintype "passive"))
      (node (ref "U8") (pin "6") (pinfunction "GND_6") (pintype "passive"))
    )
    (net (code "29") (name "Net-(*1-3V3)") (class "Default")
      (node (ref "*1") (pin "4") (pinfunction "3V3_4") (pintype "passive"))
      (node (ref "J2") (pin "2") (pintype "passive"))
    )
    (net (code "30") (name "Net-(*3-SOC-)") (class "Default")
      (node (ref "*3") (pin "-") (pinfunction "SOC-_-") (pintype "passive"))
      (node (ref "Q4") (pin "D") (pinfunction "D_D") (pintype "passive"))
    )
    (net (code "31") (name "Net-(*4-SOC+)") (class "Default")
      (node (ref "*2") (pin "1") (pintype "passive"))
      (node (ref "*4") (pin "+") (pinfunction "SOC+_+") (pintype "passive"))
    )
    (net (code "32") (name "Net-(*5-SOC+)") (class "Default")
      (node (ref "*5") (pin "+") (pinfunction "SOC+_+") (pintype "passive"))
      (node (ref "*6") (pin "+") (pinfunction "SOC+_+") (pintype "passive"))
    )
    (net (code "33") (name "Net-(*7-SOC-)") (class "Default")
      (node (ref "*7") (pin "-") (pinfunction "SOC-_-") (pintype "passive"))
      (node (ref "Q5") (pin "D") (pinfunction "D_D") (pintype "passive"))
    )
    (net (code "34") (name "Net-(D1-A)") (class "Default")
      (node (ref "D1") (pin "1") (pinfunction "A_1") (pintype "passive"))
      (node (ref "LS1") (pin "2") (pinfunction "2_2") (pintype "passive"))
      (node (ref "Q3") (pin "3") (pinfunction "C_3") (pintype "passive"))
    )
    (net (code "35") (name "Net-(D2-A)") (class "Default")
      (node (ref "D2") (pin "1") (pinfunction "A_1") (pintype "passive"))
      (node (ref "R12") (pin "2") (pinfunction "2_2") (pintype "passive"))
    )
    (net (code "36") (name "Net-(D3-A)") (class "Default")
      (node (ref "D3") (pin "1") (pinfunction "A_1") (pintype "passive"))
      (node (ref "R17") (pin "2") (pinfunction "2_2") (pintype "passive"))
    )
    (net (code "37") (name "Net-(D4-A)") (class "Default")
      (node (ref "D4") (pin "1") (pinfunction "A_1") (pintype "passive"))
      (node (ref "R18") (pin "1") (pinfunction "1_1") (pintype "passive"))
    )
    (net (code "38") (name "Net-(D5-A)") (class "Default")
      (node (ref "D5") (pin "1") (pinfunction "A_1") (pintype "passive"))
      (node (ref "R20") (pin "1") (pinfunction "1_1") (pintype "passive"))
    )
    (net (code "39") (name "Net-(H2-VCC)") (class "Default")
      (node (ref "C21") (pin "1") (pinfunction "1_1") (pintype "passive"))
      (node (ref "C22") (pin "+") (pinfunction "+_+") (pintype "passive"))
      (node (ref "H2") (pin "2") (pinfunction "VCC_2") (pintype "passive"))
      (node (ref "H3") (pin "2") (pinfunction "VCC_2") (pintype "passive"))
      (node (ref "H4") (pin "2") (pinfunction "VCC_2") (pintype "passive"))
    )
    (net (code "40") (name "Net-(IC3-SHDN)") (class "Default")
      (node (ref "IC3") (pin "4") (pinfunction "SHDN_4") (pintype "passive"))
      (node (ref "R9") (pin "1") (pinfunction "1_1") (pintype "passive"))
    )
    (net (code "41") (name "Net-(Q3-B)") (class "Default")
      (node (ref "Q3") (pin "2") (pinfunction "B_2") (pintype "passive"))
      (node (ref "R6") (pin "2") (pinfunction "2_2") (pintype "passive"))
    )
    (net (code "42") (name "Net-(Q4-PadG)") (class "Default")
      (node (ref "Q4") (pin "G") (pinfunction "G_G") (pintype "passive"))
      (node (ref "R11") (pin "1") (pinfunction "1_1") (pintype "passive"))
    )
    (net (code "43") (name "Net-(Q5-PadG)") (class "Default")
      (node (ref "Q5") (pin "G") (pinfunction "G_G") (pintype "passive"))
      (node (ref "R21") (pin "2") (pinfunction "2_2") (pintype "passive"))
    )
    (net (code "44") (name "Net-(R10-1)") (class "Default")
      (node (ref "*2") (pin "2") (pintype "passive"))
      (node (ref "C23") (pin "1") (pinfunction "1_1") (pintype "passive"))
      (node (ref "R10") (pin "-") (pinfunction "1_-") (pintype "passive"))
      (node (ref "R15") (pin "1") (pinfunction "1_1") (pintype "passive"))
    )
    (net (code "45") (name "Net-(R11-Pad2)") (class "Default")
      (node (ref "R11") (pin "2") (pinfunction "2_2") (pintype "passive"))
      (node (ref "R13") (pin "1") (pinfunction "1_1") (pintype "passive"))
      (node (ref "R17") (pin "1") (pinfunction "1_1") (pintype "passive"))
      (node (ref "U7") (pin "7") (pinfunction "E_7") (pintype "passive"))
    )
    (net (code "46") (name "Net-(R14-Pad1)") (class "Default")
      (node (ref "R14") (pin "1") (pinfunction "1_1") (pintype "passive"))
      (node (ref "U7") (pin "1") (pinfunction "A_1") (pintype "passive"))
    )
    (net (code "47") (name "Net-(R19-Pad1)") (class "Default")
      (node (ref "R19") (pin "1") (pinfunction "1_1") (pintype "passive"))
      (node (ref "U7") (pin "3") (pinfunction "A_3") (pintype "passive"))
    )
    (net (code "48") (name "Net-(R20-Pad2)") (class "Default")
      (node (ref "R20") (pin "2") (pinfunction "2_2") (pintype "passive"))
      (node (ref "R21") (pin "1") (pinfunction "1_1") (pintype "passive"))
      (node (ref "R22") (pin "2") (pinfunction "2_2") (pintype "passive"))
      (node (ref "U7") (pin "5") (pinfunction "E_5") (pintype "passive"))
    )
    (net (code "49") (name "Net-(U2-C1)") (class "Default")
      (node (ref "C9") (pin "1") (pinfunction "1_1") (pintype "passive"))
      (node (ref "U2") (pin "10") (pinfunction "C1_10") (pintype "passive"))
    )
    (net (code "50") (name "Net-(U2-SETC)") (class "Default")
      (node (ref "C10") (pin "2") (pinfunction "2_2") (pintype "passive"))
      (node (ref "U2") (pin "12") (pinfunction "SETC_12") (pintype "passive"))
    )
    (net (code "51") (name "Net-(U2-SETP)") (class "Default")
      (node (ref "C10") (pin "1") (pinfunction "1_1") (pintype "passive"))
      (node (ref "U2") (pin "8") (pinfunction "SETP_8") (pintype "passive"))
    )
    (net (code "52") (name "Net-(U3-CPOUT)") (class "Default")
      (node (ref "C8") (pin "1") (pinfunction "1_1") (pintype "passive"))
      (node (ref "U3") (pin "20") (pinfunction "CPOUT_20") (pintype "passive"))
    )
    (net (code "53") (name "Net-(U3-REGOUT)") (class "Default")
      (node (ref "C7") (pin "1") (pinfunction "1_1") (pintype "passive"))
      (node (ref "U3") (pin "10") (pinfunction "REGOUT_10") (pintype "passive"))
    )
    (net (code "54") (name "Net-(U3-VLOGIC)") (class "Default")
      (node (ref "C6") (pin "1") (pinfunction "1_1") (pintype "passive"))
      (node (ref "U3") (pin "8") (pinfunction "VLOGIC_8") (pintype "passive"))
    )
    (net (code "55") (name "Net-(U4-CSB)") (class "Default")
      (node (ref "J1") (pin "2") (pintype "passive"))
      (node (ref "U4") (pin "5") (pinfunction "CSB_5") (pintype "passive"))
    )
    (net (code "56") (name "Net-(U6-CAP)") (class "Default")
      (node (ref "C13") (pin "1") (pinfunction "1_1") (pintype "passive"))
      (node (ref "U6") (pin "2") (pinfunction "CAP_2") (pintype "passive"))
    )
    (net (code "57") (name "Net-(U6-SHDN)") (class "Default")
      (node (ref "R5") (pin "2") (pinfunction "2_2") (pintype "passive"))
      (node (ref "U6") (pin "4") (pinfunction "SHDN_4") (pintype "passive"))
    )
    (net (code "58") (name "Net-(U8-IN+)") (class "Default")
      (node (ref "R15") (pin "2") (pinfunction "2_2") (pintype "passive"))
      (node (ref "U8") (pin "8") (pinfunction "IN+_8") (pintype "passive"))
    )
    (net (code "59") (name "Net-(U8-IN-)") (class "Default")
      (node (ref "R16") (pin "2") (pinfunction "2_2") (pintype "passive"))
      (node (ref "U8") (pin "7") (pinfunction "IN-_7") (pintype "passive"))
    )
    (net (code "60") (name "VIN") (class "Default")
      (node (ref "C11") (pin "1") (pinfunction "1_1") (pintype "passive"))
      (node (ref "C17") (pin "+") (pinfunction "+_+") (pintype "passive"))
      (node (ref "C18") (pin "2") (pinfunction "2_2") (pintype "passive"))
      (node (ref "C23") (pin "2") (pinfunction "2_2") (pintype "passive"))
      (node (ref "D1") (pin "2") (pinfunction "K_2") (pintype "passive"))
      (node (ref "IC1") (pin "16") (pinfunction "VIN_16") (pintype "passive"))
      (node (ref "IC3") (pin "3") (pinfunction "VIN_3") (pintype "passive"))
      (node (ref "LS1") (pin "1") (pinfunction "1_1") (pintype "passive"))
      (node (ref "R10") (pin "+") (pinfunction "2_+") (pintype "passive"))
      (node (ref "R16") (pin "1") (pinfunction "1_1") (pintype "passive"))
      (node (ref "R9") (pin "2") (pinfunction "2_2") (pintype "passive"))
    )
    (net (code "61") (name "VPYRO") (class "Default")
      (node (ref "*3") (pin "+") (pinfunction "SOC+_+") (pintype "passive"))
      (node (ref "*6") (pin "-") (pinfunction "SOC-_-") (pintype "passive"))
      (node (ref "*7") (pin "+") (pinfunction "SOC+_+") (pintype "passive"))
      (node (ref "U7") (pin "6") (pinfunction "C_6") (pintype "passive"))
      (node (ref "U7") (pin "8") (pinfunction "C_8") (pintype "passive"))
    )
    (net (code "62") (name "VPYROGND") (class "Default")
      (node (ref "*5") (pin "-") (pinfunction "SOC-_-") (pintype "passive"))
      (node (ref "D3") (pin "2") (pinfunction "K_2") (pintype "passive"))
      (node (ref "D5") (pin "2") (pinfunction "K_2") (pintype "passive"))
      (node (ref "Q4") (pin "S") (pinfunction "S_S") (pintype "passive"))
      (node (ref "Q5") (pin "S") (pinfunction "S_S") (pintype "passive"))
      (node (ref "R13") (pin "2") (pinfunction "2_2") (pintype "passive"))
      (node (ref "R22") (pin "1") (pinfunction "1_1") (pintype "passive"))
    )
    (net (code "63") (name "unconnected-(*2-Pad3)") (class "Default")
      (node (ref "*2") (pin "3") (pintype "passive"))
    )
    (net (code "64") (name "unconnected-(H2-SGNL-Pad3)") (class "Default")
      (node (ref "H2") (pin "3") (pinfunction "SGNL_3") (pintype "passive"))
    )
    (net (code "65") (name "unconnected-(IC1-REF-Pad28)") (class "Default")
      (node (ref "IC1") (pin "28") (pinfunction "REF_28") (pintype "passive"))
    )
    (net (code "66") (name "unconnected-(IC1-RST-Pad3)") (class "Default")
      (node (ref "IC1") (pin "3") (pinfunction "RST_3") (pintype "passive"))
    )
    (net (code "67") (name "unconnected-(IC1-RST-Pad18)") (class "Default")
      (node (ref "IC1") (pin "18") (pinfunction "RST_18") (pintype "passive"))
    )
    (net (code "68") (name "unconnected-(J2-Pad1)") (class "Default")
      (node (ref "J2") (pin "1") (pintype "passive"))
    )
    (net (code "69") (name "unconnected-(U1-NC-Pad3)") (class "Default")
      (node (ref "U1") (pin "3") (pinfunction "NC_3") (pintype "passive"))
    )
    (net (code "70") (name "unconnected-(U1-NC-Pad10)") (class "Default")
      (node (ref "U1") (pin "10") (pinfunction "NC_10") (pintype "passive"))
    )
    (net (code "71") (name "unconnected-(U1-NC-Pad11)") (class "Default")
      (node (ref "U1") (pin "11") (pinfunction "NC_11") (pintype "passive"))
    )
    (net (code "72") (name "unconnected-(U2-DRDY-Pad15)") (class "Default")
      (node (ref "U2") (pin "15") (pinfunction "DRDY_15") (pintype "passive"))
    )
    (net (code "73") (name "unconnected-(U2-NC-Pad3)") (class "Default")
      (node (ref "U2") (pin "3") (pinfunction "NC_3") (pintype "passive"))
    )
    (net (code "74") (name "unconnected-(U2-NC-Pad5)") (class "Default")
      (node (ref "U2") (pin "5") (pinfunction "NC_5") (pintype "passive"))
    )
    (net (code "75") (name "unconnected-(U2-NC-Pad6)") (class "Default")
      (node (ref "U2") (pin "6") (pinfunction "NC_6") (pintype "passive"))
    )
    (net (code "76") (name "unconnected-(U2-NC-Pad7)") (class "Default")
      (node (ref "U2") (pin "7") (pinfunction "NC_7") (pintype "passive"))
    )
    (net (code "77") (name "unconnected-(U2-NC-Pad14)") (class "Default")
      (node (ref "U2") (pin "14") (pinfunction "NC_14") (pintype "passive"))
    )
    (net (code "78") (name "unconnected-(U4-CSB0-Pad4)") (class "Default")
      (node (ref "U4") (pin "4") (pinfunction "CSB0_4") (pintype "passive"))
    )
    (net (code "79") (name "unconnected-(U4-SDO-Pad6)") (class "Default")
      (node (ref "U4") (pin "6") (pinfunction "SDO_6") (pintype "passive"))
    )
    (net (code "80") (name "unconnected-(U5-ALERT-Pad3)") (class "Default")
      (node (ref "U5") (pin "3") (pinfunction "ALERT_3") (pintype "passive"))
    )
  )
)
